# POWER.net
KiCad netlist of a schematic drawn in Altium Designer
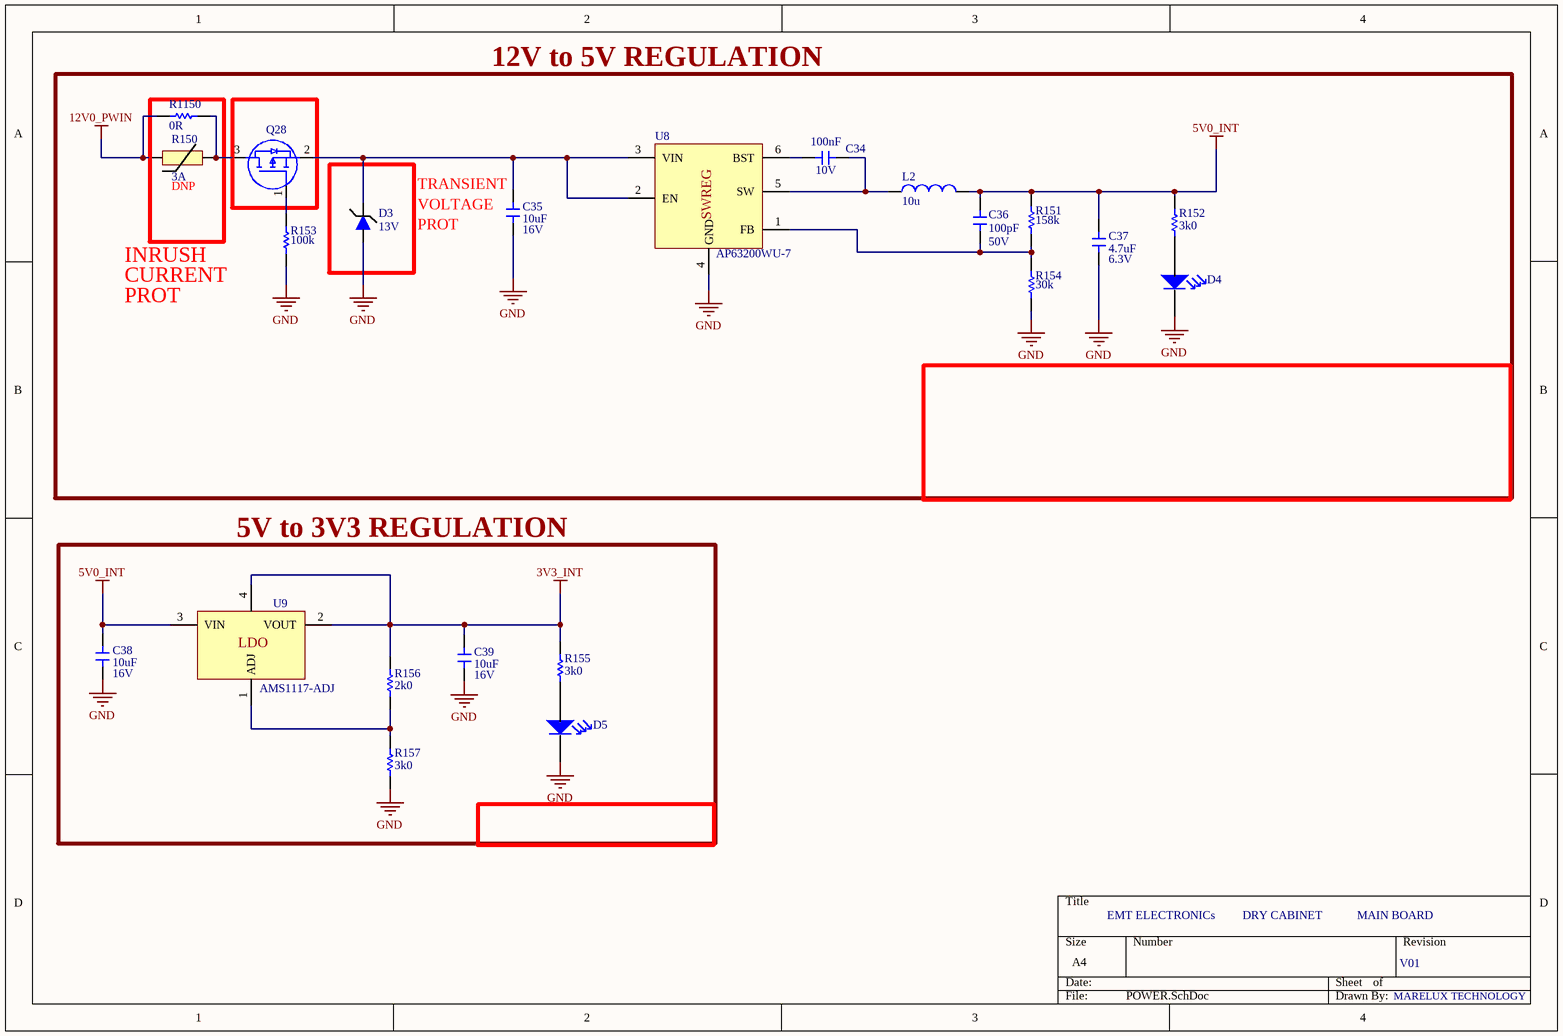
[diagram p0: POWER.SchDoc]

(export (version "E")
  (design (tool "Eeschema 10.0.6"))
  (components
    (comp (ref "C34")
      (value "100nF")
      (footprint "MareLux24Lib:CAP_0402_CER")
      (description "100nF 0402 Ceramic Capacitor")
      (fields (field (name "PART NUMBER") "CL05B104KP5NNNC") (field (name "VOLTAGE") "10V"))
      (libsource (lib "MareLux24Lib") (part "CAP_GEN_CER"))
    )
    (comp (ref "C35")
      (value "10uF")
      (footprint "CAP_0805_CER")
      (description "10uF 0805 Ceramic Capacitor")
      (fields (field (name "PART NUMBER") "CL21A106KOQNNNE") (field (name "VOLTAGE") "16V"))
      (libsource (lib "MareLux24Lib") (part "CAP_GEN_CER"))
    )
    (comp (ref "C36")
      (value "100pF")
      (footprint "MareLux24Lib:CAP_0402_CER")
      (description "100pF 0402 Ceramic Capacitor")
      (fields (field (name "PART NUMBER") "CC0402JRNPO9BN101") (field (name "VOLTAGE") "50V"))
      (libsource (lib "MareLux24Lib") (part "CAP_GEN_CER"))
    )
    (comp (ref "C37")
      (value "4.7uF")
      (footprint "MareLux24Lib:CAP_0603_CER")
      (description "4,7uF 0603 Ceramic Capacitor")
      (fields (field (name "PART NUMBER") "CL10A475KP8NNNC") (field (name "VOLTAGE") "6.3V"))
      (libsource (lib "MareLux24Lib") (part "CAP_GEN_CER"))
    )
    (comp (ref "C38")
      (value "10uF")
      (footprint "CAP_0805_CER")
      (description "10uF 0805 Ceramic Capacitor")
      (fields (field (name "PART NUMBER") "CL21A106KOQNNNE") (field (name "VOLTAGE") "16V"))
      (libsource (lib "MareLux24Lib") (part "CAP_GEN_CER"))
    )
    (comp (ref "C39")
      (value "10uF")
      (footprint "CAP_0805_CER")
      (description "10uF 0805 Ceramic Capacitor")
      (fields (field (name "PART NUMBER") "CL21A106KOQNNNE") (field (name "VOLTAGE") "16V"))
      (libsource (lib "MareLux24Lib") (part "CAP_GEN_CER"))
    )
    (comp (ref "D3")
      (value "13V")
      (footprint "SOD-123F")
      (description "TVS DIODE 200W 14.4V-15.9V SOD-123")
      (fields (field (name "PART NUMBER") "SMF13A") (field (name "VOLTAGE") "14.4V"))
      (libsource (lib "MareLux24Lib") (part "SMF13A"))
    )
    (comp (ref "D4")
      (value "HSMM-C170")
      (footprint "LED_0805_SMD")
      (fields (field (name "VOLTAGE") "3.3V") (field (name "MANUFACTURER") "Broadcom"))
      (libsource (lib "MareLux24Lib") (part "LED_GEN"))
    )
    (comp (ref "D5")
      (value "HSMM-C170")
      (footprint "LED_0805_SMD")
      (fields (field (name "VOLTAGE") "3.3V") (field (name "MANUFACTURER") "Broadcom"))
      (libsource (lib "MareLux24Lib") (part "LED_GEN"))
    )
    (comp (ref "L2")
      (value "10u")
      (footprint "IND_YAGEO")
      (description "FIXED IND 10UH 4A 68 MOHM SMD")
      (fields (field (name "PART NUMBER") "BMRB00060630100MA1") (field (name "TOLERANCE") "±20%"))
      (libsource (lib "MareLux24Lib") (part "BMRB00060630100MA1"))
    )
    (comp (ref "Q28")
      (value "GSF3407")
      (footprint "SOT-23")
      (description "P-Channel 30 V 4.1A (Ta) 1.2W (Ta) Surface Mount SOT-23")
      (fields (field (name "VOLTAGE") "30 V") (field (name "POWER") "1200 mW"))
      (libsource (lib "MareLux24Lib") (part "GSF3407"))
    )
    (comp (ref "R150")
      (value "3A")
      (footprint "MF72-005D9")
      (description "Inrush Current Limiter 5 Ohms ±20% 3 A")
      (fields
        (field (name "PART NUMBER") "MF72-005D9")
        (field (name "TOLERANCE") "20")
        (field (name "PLACE") "DNP")
      )
      (libsource (lib "MareLux24Lib") (part "MF72-005D9"))
    )
    (comp (ref "R151")
      (value "158k")
      (footprint "MareLux24Lib:RES_0402_SMD")
      (description "Generic Chip Res 158k")
      (fields (field (name "PART NUMBER") "RMCF0402FT158K") (field (name "TOLERANCE") "1%"))
      (libsource (lib "MareLux24Lib") (part "RES_GEN_SMD"))
    )
    (comp (ref "R152")
      (value "3k0")
      (footprint "MareLux24Lib:RES_0402_SMD")
      (description "Generic Chip Res 3k0")
      (fields (field (name "PART NUMBER") "RMCF0402FT3K00") (field (name "TOLERANCE") "1 %"))
      (libsource (lib "MareLux24Lib") (part "RES_GEN_SMD"))
    )
    (comp (ref "R153")
      (value "100k")
      (footprint "MareLux24Lib:RES_0402_SMD")
      (description "Generic Chip Res 158k")
      (fields (field (name "PART NUMBER") "RMCF0402JT100K") (field (name "TOLERANCE") "5%"))
      (libsource (lib "MareLux24Lib") (part "RES_GEN_SMD"))
    )
    (comp (ref "R154")
      (value "30k")
      (footprint "MareLux24Lib:RES_0402_SMD")
      (description "Generic Chip Res 30k")
      (fields (field (name "PART NUMBER") "RMCF0402JT30K0") (field (name "TOLERANCE") "5%"))
      (libsource (lib "MareLux24Lib") (part "RES_GEN_SMD"))
    )
    (comp (ref "R155")
      (value "3k0")
      (footprint "MareLux24Lib:RES_0402_SMD")
      (description "Generic Chip Res 3k0")
      (fields (field (name "PART NUMBER") "RMCF0402FT3K00") (field (name "TOLERANCE") "1 %"))
      (libsource (lib "MareLux24Lib") (part "RES_GEN_SMD"))
    )
    (comp (ref "R156")
      (value "2k0")
      (footprint "MareLux24Lib:RES_0402_SMD")
      (description "Generic Chip Res 2k0")
      (fields (field (name "PART NUMBER") "RMCF0402FT2K00") (field (name "TOLERANCE") "1 %"))
      (libsource (lib "MareLux24Lib") (part "RES_GEN_SMD"))
    )
    (comp (ref "R157")
      (value "3k0")
      (footprint "MareLux24Lib:RES_0402_SMD")
      (description "Generic Chip Res 3k0")
      (fields (field (name "PART NUMBER") "RMCF0402FT3K00") (field (name "TOLERANCE") "1 %"))
      (libsource (lib "MareLux24Lib") (part "RES_GEN_SMD"))
    )
    (comp (ref "R1150")
      (value "0R")
      (footprint "RES_1206_SMD")
      (description "Generic Chip Res 0R")
      (libsource (lib "MareLux24Lib") (part "RES_GEN_SMD"))
    )
    (comp (ref "U8")
      (value "AP63200WU-7")
      (footprint "TSOT-23-6")
      (description "IC REG BUCK ADJ 2A TSOT23-6\r\n3.8V to 32V")
      (fields (field (name "VOLTAGE") "ADJ") (field (name "MANUFACTURER") "Diodes Incorporated"))
      (libsource (lib "MareLux24Lib") (part "AP63200WU-7"))
    )
    (comp (ref "U9")
      (value "AMS1117-ADJ")
      (footprint "SOT-223-3")
      (description "IC LDO REG ADJ 1A SOT223")
      (fields (field (name "VOLTAGE") "ADJ") (field (name "MANUFACTURER") "EVVO"))
      (libsource (lib "MareLux24Lib") (part "AMS1117-ADJ"))
    )
  )
  (nets
    (net (code "1") (name "3V3_INT") (class "Default")
      (node (ref "C39") (pin "2") (pinfunction "2_2") (pintype "passive"))
      (node (ref "R155") (pin "2") (pinfunction "2_2") (pintype "passive"))
      (node (ref "R156") (pin "2") (pinfunction "2_2") (pintype "passive"))
      (node (ref "U9") (pin "2") (pinfunction "VOUT_2") (pintype "power_in"))
      (node (ref "U9") (pin "4") (pinfunction "OUT_4") (pintype "power_in"))
    )
    (net (code "2") (name "5V0_INT") (class "Default")
      (node (ref "C36") (pin "1") (pinfunction "1_1") (pintype "passive"))
      (node (ref "C37") (pin "2") (pinfunction "2_2") (pintype "passive"))
      (node (ref "C38") (pin "2") (pinfunction "2_2") (pintype "passive"))
      (node (ref "L2") (pin "2") (pinfunction "2_2") (pintype "passive"))
      (node (ref "R151") (pin "2") (pinfunction "2_2") (pintype "passive"))
      (node (ref "R152") (pin "2") (pinfunction "2_2") (pintype "passive"))
      (node (ref "U9") (pin "3") (pinfunction "VIN_3") (pintype "power_in"))
    )
    (net (code "3") (name "12V0_PWIN") (class "Default")
      (node (ref "R1150") (pin "1") (pinfunction "1_1") (pintype "passive"))
      (node (ref "R150") (pin "1") (pinfunction "1_1") (pintype "passive"))
    )
    (net (code "4") (name "GND") (class "Default")
      (node (ref "C35") (pin "1") (pinfunction "1_1") (pintype "passive"))
      (node (ref "C37") (pin "1") (pinfunction "1_1") (pintype "passive"))
      (node (ref "C38") (pin "1") (pinfunction "1_1") (pintype "passive"))
      (node (ref "C39") (pin "1") (pinfunction "1_1") (pintype "passive"))
      (node (ref "D3") (pin "2") (pinfunction "A_2") (pintype "passive"))
      (node (ref "D4") (pin "C") (pinfunction "C_C") (pintype "passive"))
      (node (ref "D5") (pin "C") (pinfunction "C_C") (pintype "passive"))
      (node (ref "R153") (pin "1") (pinfunction "1_1") (pintype "passive"))
      (node (ref "R154") (pin "1") (pinfunction "1_1") (pintype "passive"))
      (node (ref "R157") (pin "1") (pinfunction "1_1") (pintype "passive"))
      (node (ref "U8") (pin "4") (pinfunction "GND_4") (pintype "power_in"))
    )
    (net (code "5") (name "Net-(D3-C)") (class "Default")
      (node (ref "C35") (pin "2") (pinfunction "2_2") (pintype "passive"))
      (node (ref "D3") (pin "1") (pinfunction "C_1") (pintype "passive"))
      (node (ref "Q28") (pin "2") (pinfunction "S_2") (pintype "passive"))
      (node (ref "U8") (pin "2") (pinfunction "EN_2") (pintype "passive"))
      (node (ref "U8") (pin "3") (pinfunction "VIN_3") (pintype "passive"))
    )
    (net (code "6") (name "Net-(D4-PadA)") (class "Default")
      (node (ref "D4") (pin "A") (pinfunction "A_A") (pintype "passive"))
      (node (ref "R152") (pin "1") (pinfunction "1_1") (pintype "passive"))
    )
    (net (code "7") (name "Net-(D5-PadA)") (class "Default")
      (node (ref "D5") (pin "A") (pinfunction "A_A") (pintype "passive"))
      (node (ref "R155") (pin "1") (pinfunction "1_1") (pintype "passive"))
    )
    (net (code "8") (name "Net-(Q28-D)") (class "Default")
      (node (ref "Q28") (pin "3") (pinfunction "D_3") (pintype "passive"))
      (node (ref "R1150") (pin "2") (pinfunction "2_2") (pintype "passive"))
      (node (ref "R150") (pin "2") (pinfunction "2_2") (pintype "passive"))
    )
    (net (code "9") (name "Net-(Q28-G)") (class "Default")
      (node (ref "Q28") (pin "1") (pinfunction "G_1") (pintype "passive"))
      (node (ref "R153") (pin "2") (pinfunction "2_2") (pintype "passive"))
    )
    (net (code "10") (name "Net-(U8-BST)") (class "Default")
      (node (ref "C34") (pin "2") (pinfunction "2_2") (pintype "passive"))
      (node (ref "U8") (pin "6") (pinfunction "BST_6") (pintype "passive"))
    )
    (net (code "11") (name "Net-(U8-FB)") (class "Default")
      (node (ref "C36") (pin "2") (pinfunction "2_2") (pintype "passive"))
      (node (ref "R151") (pin "1") (pinfunction "1_1") (pintype "passive"))
      (node (ref "R154") (pin "2") (pinfunction "2_2") (pintype "passive"))
      (node (ref "U8") (pin "1") (pinfunction "FB_1") (pintype "passive"))
    )
    (net (code "12") (name "Net-(U8-SW)") (class "Default")
      (node (ref "C34") (pin "1") (pinfunction "1_1") (pintype "passive"))
      (node (ref "L2") (pin "1") (pinfunction "1_1") (pintype "passive"))
      (node (ref "U8") (pin "5") (pinfunction "SW_5") (pintype "passive"))
    )
    (net (code "13") (name "Net-(U9-ADJ)") (class "Default")
      (node (ref "R156") (pin "1") (pinfunction "1_1") (pintype "passive"))
      (node (ref "R157") (pin "2") (pinfunction "2_2") (pintype "passive"))
      (node (ref "U9") (pin "1") (pinfunction "ADJ_1") (pintype "power_in"))
    )
  )
)
